# lettore_corrente_v1.net
KiCad netlist of a schematic drawn in EAGLE
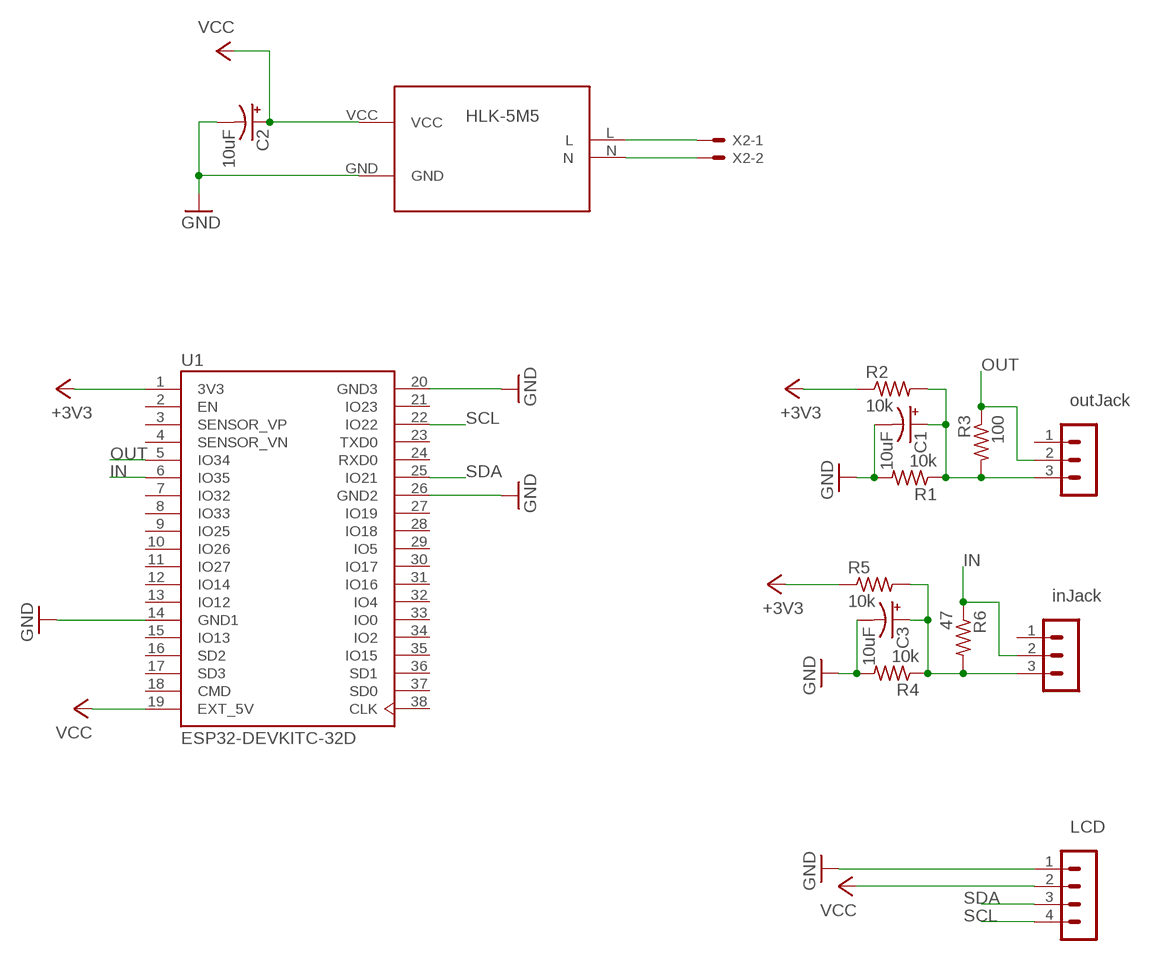
[diagram p0: schematic, sheet 1]

(export (version "E")
  (design (tool "Eeschema 10.0.6"))
  (components
    (comp (ref "C1")
      (value "10uF")
      (footprint "eagle-import:B45181A")
      (libsource (lib "eagle-import") (part "CPOL-USB45181A"))
    )
    (comp (ref "C2")
      (value "10uF")
      (footprint "eagle-import:B45181A")
      (libsource (lib "eagle-import") (part "CPOL-USB45181A"))
    )
    (comp (ref "C3")
      (value "10uF")
      (footprint "eagle-import:B45181A")
      (libsource (lib "eagle-import") (part "CPOL-USB45181A"))
    )
    (comp (ref "HLK-5M5")
      (value "HLK-5M05")
      (footprint "eagle-import:CONV_HLK-5M05")
      (libsource (lib "eagle-import") (part "HLK-5M05"))
    )
    (comp (ref "R1")
      (value "10k")
      (footprint "eagle-import:0204_7")
      (libsource (lib "eagle-import") (part "R-US_0204/7"))
    )
    (comp (ref "R2")
      (value "10k")
      (footprint "eagle-import:0204_7")
      (libsource (lib "eagle-import") (part "R-US_0204/7"))
    )
    (comp (ref "R3")
      (value "100")
      (footprint "eagle-import:0204_7")
      (libsource (lib "eagle-import") (part "R-US_0204/7"))
    )
    (comp (ref "R4")
      (value "10k")
      (footprint "eagle-import:0204_7")
      (libsource (lib "eagle-import") (part "R-US_0204/7"))
    )
    (comp (ref "R5")
      (value "10k")
      (footprint "eagle-import:0204_7")
      (libsource (lib "eagle-import") (part "R-US_0204/7"))
    )
    (comp (ref "R6")
      (value "47")
      (footprint "eagle-import:0204_7")
      (libsource (lib "eagle-import") (part "R-US_0204/7"))
    )
    (comp (ref "SV1")
      (value "MA03-1")
      (footprint "eagle-import:MA03-1")
      (libsource (lib "eagle-import") (part "MA03-1"))
    )
    (comp (ref "SV2")
      (value "MA03-1")
      (footprint "eagle-import:MA03-1")
      (libsource (lib "eagle-import") (part "MA03-1"))
    )
    (comp (ref "SV3")
      (value "MA04-1")
      (footprint "eagle-import:MA04-1")
      (libsource (lib "eagle-import") (part "MA04-1"))
    )
    (comp (ref "U1")
      (value "ESP32-DEVKITC-32D")
      (footprint "eagle-import:MODULE_ESP32-DEVKITC-32D")
      (fields (field (name "MF") "Espressif Systems"))
      (libsource (lib "eagle-import") (part "ESP32-DEVKITC-32D"))
    )
    (comp (ref "X2")
      (value "JST-XH-02-PIN-LONG-PAD")
      (footprint "eagle-import:JST-XH-02-PACKAGE-LONG-PAD")
      (libsource (lib "eagle-import") (part "JST-XH-02-PIN-LONG-PAD"))
    )
  )
  (nets
    (net (code "1") (name "+3V3") (class "Default")
      (node (ref "R2") (pin "1") (pinfunction "1_1") (pintype "passive"))
      (node (ref "R5") (pin "1") (pinfunction "1_1") (pintype "passive"))
      (node (ref "U1") (pin "1") (pinfunction "3V3_1") (pintype "power_in"))
    )
    (net (code "2") (name "/IN") (class "Default")
      (node (ref "R6") (pin "1") (pinfunction "1_1") (pintype "passive"))
      (node (ref "SV2") (pin "2") (pinfunction "2_2") (pintype "passive"))
      (node (ref "U1") (pin "6") (pinfunction "IO35_6") (pintype "bidirectional"))
    )
    (net (code "3") (name "/OUT") (class "Default")
      (node (ref "R3") (pin "1") (pinfunction "1_1") (pintype "passive"))
      (node (ref "SV1") (pin "2") (pinfunction "2_2") (pintype "passive"))
      (node (ref "U1") (pin "5") (pinfunction "IO34_5") (pintype "bidirectional"))
    )
    (net (code "4") (name "/SCL") (class "Default")
      (node (ref "SV3") (pin "4") (pinfunction "4_4") (pintype "passive"))
      (node (ref "U1") (pin "22") (pinfunction "IO22_22") (pintype "bidirectional"))
    )
    (net (code "5") (name "/SDA") (class "Default")
      (node (ref "SV3") (pin "3") (pinfunction "3_3") (pintype "passive"))
      (node (ref "U1") (pin "25") (pinfunction "IO21_25") (pintype "bidirectional"))
    )
    (net (code "6") (name "GND") (class "Default")
      (node (ref "C1") (pin "-") (pinfunction "-_-") (pintype "passive"))
      (node (ref "C2") (pin "-") (pinfunction "-_-") (pintype "passive"))
      (node (ref "C3") (pin "-") (pinfunction "-_-") (pintype "passive"))
      (node (ref "HLK-5M5") (pin "GND") (pinfunction "GND_GND") (pintype "bidirectional"))
      (node (ref "R1") (pin "2") (pinfunction "2_2") (pintype "passive"))
      (node (ref "R4") (pin "2") (pinfunction "2_2") (pintype "passive"))
      (node (ref "SV3") (pin "1") (pinfunction "1_1") (pintype "passive"))
      (node (ref "U1") (pin "14") (pinfunction "GND1_14") (pintype "power_in"))
      (node (ref "U1") (pin "20") (pinfunction "GND3_20") (pintype "power_in"))
      (node (ref "U1") (pin "26") (pinfunction "GND2_26") (pintype "power_in"))
    )
    (net (code "7") (name "Net-(C1-Pad+)") (class "Default")
      (node (ref "C1") (pin "+") (pinfunction "+_+") (pintype "passive"))
      (node (ref "R1") (pin "1") (pinfunction "1_1") (pintype "passive"))
      (node (ref "R2") (pin "2") (pinfunction "2_2") (pintype "passive"))
      (node (ref "R3") (pin "2") (pinfunction "2_2") (pintype "passive"))
      (node (ref "SV1") (pin "3") (pinfunction "3_3") (pintype "passive"))
    )
    (net (code "8") (name "Net-(C3-Pad+)") (class "Default")
      (node (ref "C3") (pin "+") (pinfunction "+_+") (pintype "passive"))
      (node (ref "R4") (pin "1") (pinfunction "1_1") (pintype "passive"))
      (node (ref "R5") (pin "2") (pinfunction "2_2") (pintype "passive"))
      (node (ref "R6") (pin "2") (pinfunction "2_2") (pintype "passive"))
      (node (ref "SV2") (pin "3") (pinfunction "3_3") (pintype "passive"))
    )
    (net (code "9") (name "Net-(X2A-S)") (class "Default")
      (node (ref "HLK-5M5") (pin "L") (pinfunction "L_L") (pintype "bidirectional"))
      (node (ref "X2") (pin "1") (pinfunction "S_1") (pintype "passive"))
    )
    (net (code "10") (name "Net-(X2B-S)") (class "Default")
      (node (ref "HLK-5M5") (pin "N") (pinfunction "N_N") (pintype "bidirectional"))
      (node (ref "X2") (pin "2") (pinfunction "S_2") (pintype "passive"))
    )
    (net (code "11") (name "VCC") (class "Default")
      (node (ref "C2") (pin "+") (pinfunction "+_+") (pintype "passive"))
      (node (ref "HLK-5M5") (pin "VCC") (pinfunction "VCC_VCC") (pintype "bidirectional"))
      (node (ref "SV3") (pin "2") (pinfunction "2_2") (pintype "passive"))
      (node (ref "U1") (pin "19") (pinfunction "EXT_5V_19") (pintype "power_in"))
    )
    (net (code "12") (name "unconnected-(SV1-Pad1)") (class "Default")
      (node (ref "SV1") (pin "1") (pinfunction "1_1") (pintype "passive"))
    )
    (net (code "13") (name "unconnected-(SV2-Pad1)") (class "Default")
      (node (ref "SV2") (pin "1") (pinfunction "1_1") (pintype "passive"))
    )
    (net (code "14") (name "unconnected-(U1-CLK-Pad38)") (class "Default")
      (node (ref "U1") (pin "38") (pinfunction "CLK_38") (pintype "input"))
    )
    (net (code "15") (name "unconnected-(U1-CMD-Pad18)") (class "Default")
      (node (ref "U1") (pin "18") (pinfunction "CMD_18") (pintype "bidirectional"))
    )
    (net (code "16") (name "unconnected-(U1-EN-Pad2)") (class "Default")
      (node (ref "U1") (pin "2") (pinfunction "EN_2") (pintype "input"))
    )
    (net (code "17") (name "unconnected-(U1-IO0-Pad33)") (class "Default")
      (node (ref "U1") (pin "33") (pinfunction "IO0_33") (pintype "bidirectional"))
    )
    (net (code "18") (name "unconnected-(U1-IO2-Pad34)") (class "Default")
      (node (ref "U1") (pin "34") (pinfunction "IO2_34") (pintype "bidirectional"))
    )
    (net (code "19") (name "unconnected-(U1-IO4-Pad32)") (class "Default")
      (node (ref "U1") (pin "32") (pinfunction "IO4_32") (pintype "bidirectional"))
    )
    (net (code "20") (name "unconnected-(U1-IO5-Pad29)") (class "Default")
      (node (ref "U1") (pin "29") (pinfunction "IO5_29") (pintype "bidirectional"))
    )
    (net (code "21") (name "unconnected-(U1-IO12-Pad13)") (class "Default")
      (node (ref "U1") (pin "13") (pinfunction "IO12_13") (pintype "bidirectional"))
    )
    (net (code "22") (name "unconnected-(U1-IO13-Pad15)") (class "Default")
      (node (ref "U1") (pin "15") (pinfunction "IO13_15") (pintype "bidirectional"))
    )
    (net (code "23") (name "unconnected-(U1-IO14-Pad12)") (class "Default")
      (node (ref "U1") (pin "12") (pinfunction "IO14_12") (pintype "bidirectional"))
    )
    (net (code "24") (name "unconnected-(U1-IO15-Pad35)") (class "Default")
      (node (ref "U1") (pin "35") (pinfunction "IO15_35") (pintype "bidirectional"))
    )
    (net (code "25") (name "unconnected-(U1-IO16-Pad31)") (class "Default")
      (node (ref "U1") (pin "31") (pinfunction "IO16_31") (pintype "bidirectional"))
    )
    (net (code "26") (name "unconnected-(U1-IO17-Pad30)") (class "Default")
      (node (ref "U1") (pin "30") (pinfunction "IO17_30") (pintype "bidirectional"))
    )
    (net (code "27") (name "unconnected-(U1-IO18-Pad28)") (class "Default")
      (node (ref "U1") (pin "28") (pinfunction "IO18_28") (pintype "bidirectional"))
    )
    (net (code "28") (name "unconnected-(U1-IO19-Pad27)") (class "Default")
      (node (ref "U1") (pin "27") (pinfunction "IO19_27") (pintype "bidirectional"))
    )
    (net (code "29") (name "unconnected-(U1-IO23-Pad21)") (class "Default")
      (node (ref "U1") (pin "21") (pinfunction "IO23_21") (pintype "bidirectional"))
    )
    (net (code "30") (name "unconnected-(U1-IO25-Pad9)") (class "Default")
      (node (ref "U1") (pin "9") (pinfunction "IO25_9") (pintype "bidirectional"))
    )
    (net (code "31") (name "unconnected-(U1-IO26-Pad10)") (class "Default")
      (node (ref "U1") (pin "10") (pinfunction "IO26_10") (pintype "bidirectional"))
    )
    (net (code "32") (name "unconnected-(U1-IO27-Pad11)") (class "Default")
      (node (ref "U1") (pin "11") (pinfunction "IO27_11") (pintype "bidirectional"))
    )
    (net (code "33") (name "unconnected-(U1-IO32-Pad7)") (class "Default")
      (node (ref "U1") (pin "7") (pinfunction "IO32_7") (pintype "bidirectional"))
    )
    (net (code "34") (name "unconnected-(U1-IO33-Pad8)") (class "Default")
      (node (ref "U1") (pin "8") (pinfunction "IO33_8") (pintype "bidirectional"))
    )
    (net (code "35") (name "unconnected-(U1-RXD0-Pad24)") (class "Default")
      (node (ref "U1") (pin "24") (pinfunction "RXD0_24") (pintype "input"))
    )
    (net (code "36") (name "unconnected-(U1-SD0-Pad37)") (class "Default")
      (node (ref "U1") (pin "37") (pinfunction "SD0_37") (pintype "bidirectional"))
    )
    (net (code "37") (name "unconnected-(U1-SD1-Pad36)") (class "Default")
      (node (ref "U1") (pin "36") (pinfunction "SD1_36") (pintype "bidirectional"))
    )
    (net (code "38") (name "unconnected-(U1-SD2-Pad16)") (class "Default")
      (node (ref "U1") (pin "16") (pinfunction "SD2_16") (pintype "bidirectional"))
    )
    (net (code "39") (name "unconnected-(U1-SD3-Pad17)") (class "Default")
      (node (ref "U1") (pin "17") (pinfunction "SD3_17") (pintype "bidirectional"))
    )
    (net (code "40") (name "unconnected-(U1-SENSOR_VN-Pad4)") (class "Default")
      (node (ref "U1") (pin "4") (pinfunction "SENSOR_VN_4") (pintype "input"))
    )
    (net (code "41") (name "unconnected-(U1-SENSOR_VP-Pad3)") (class "Default")
      (node (ref "U1") (pin "3") (pinfunction "SENSOR_VP_3") (pintype "input"))
    )
    (net (code "42") (name "unconnected-(U1-TXD0-Pad23)") (class "Default")
      (node (ref "U1") (pin "23") (pinfunction "TXD0_23") (pintype "output"))
    )
  )
)
